# io.net
KiCad netlist of a schematic drawn in Altium Designer
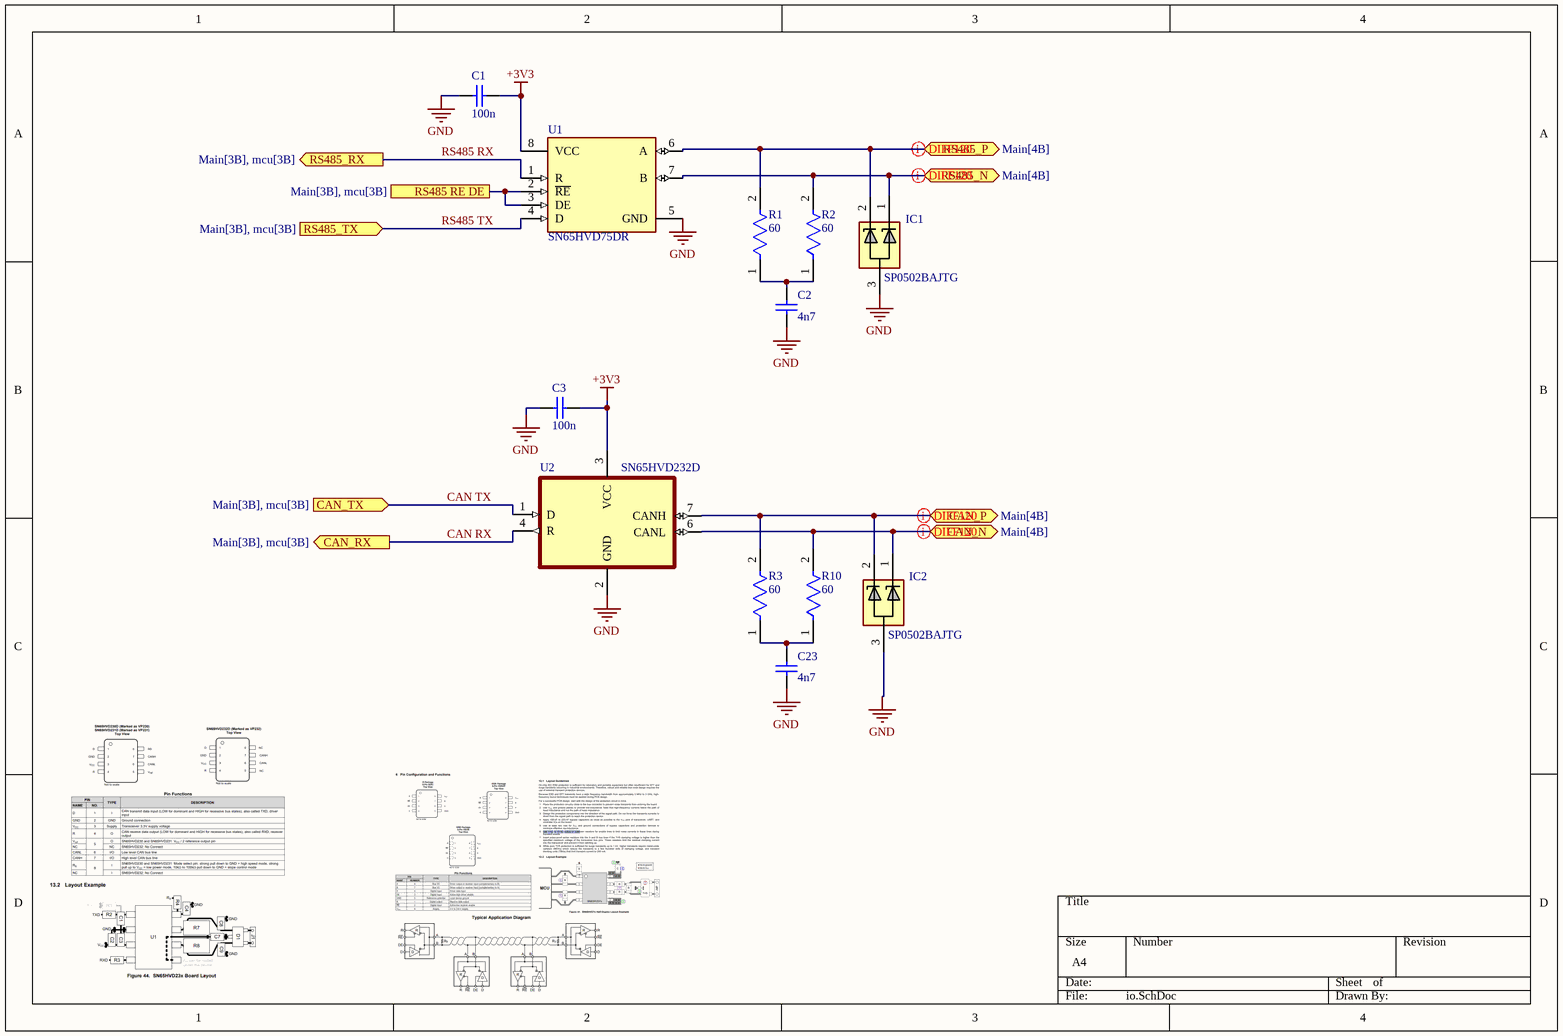
[diagram p0: io.SchDoc]

(export (version "E")
  (design (tool "Eeschema 10.0.6"))
  (components
    (comp (ref "C1")
      (value "100n")
      (footprint "CAPC1206(3216)170_M")
      (description "CAP 47nF 200V ±10% 1206 (3216 Metric) Thickness 1.7mm SMD")
      (fields (field (name "TOLERANCE") "Â±10%"))
      (libsource (lib "Altium Content Vault") (part "CAP"))
    )
    (comp (ref "C2")
      (value "4n7")
      (footprint "CAPC1206(3216)150_L")
      (description "CAP 1.8uF 10V ±5% 1206 (3216 Metric) Thickness 1.45mm SMD")
      (fields (field (name "TOLERANCE") "Â±5%"))
      (libsource (lib "Altium Content Vault") (part "CAP"))
    )
    (comp (ref "C3")
      (value "100n")
      (footprint "CAPC1206(3216)170_M")
      (description "CAP 47nF 200V ±10% 1206 (3216 Metric) Thickness 1.7mm SMD")
      (fields (field (name "TOLERANCE") "Â±10%"))
      (libsource (lib "Altium Content Vault") (part "CAP"))
    )
    (comp (ref "C23")
      (value "4n7")
      (footprint "CAPC1206(3216)150_L")
      (description "CAP 1.8uF 10V ±5% 1206 (3216 Metric) Thickness 1.45mm SMD")
      (fields (field (name "TOLERANCE") "Â±5%"))
      (libsource (lib "Altium Content Vault") (part "CAP"))
    )
    (comp (ref "IC1")
      (value "SP0502BAJTG")
      (footprint "SOT132P220X110-3N")
      (description "Integrated Circuit")
      (fields (field (name "MOUSER PART NUMBER") "576-SP0502BAJTG"))
      (libsource (lib "HydrogreenLibrary") (part "SP0502BAJTG"))
    )
    (comp (ref "IC2")
      (value "SP0502BAJTG")
      (footprint "SOT132P220X110-3N")
      (description "Integrated Circuit")
      (fields (field (name "MOUSER PART NUMBER") "576-SP0502BAJTG"))
      (libsource (lib "HydrogreenLibrary") (part "SP0502BAJTG"))
    )
    (comp (ref "R1")
      (value "60")
      (footprint "FP-RK73H2B-MFG")
      (description "40.2kΩ ±1% 0.25W Chip Resistor 1206 Thick Film AEC-Q200 Qualified")
      (fields (field (name "TOLERANCE") "1%"))
      (libsource (lib "Altium Content Vault") (part "1029c3af85768c4190bb7ad29bc67b5"))
    )
    (comp (ref "R2")
      (value "60")
      (footprint "FP-RK73H2B-MFG")
      (description "40.2kΩ ±1% 0.25W Chip Resistor 1206 Thick Film AEC-Q200 Qualified")
      (fields (field (name "TOLERANCE") "1%"))
      (libsource (lib "Altium Content Vault") (part "1029c3af85768c4190bb7ad29bc67b5"))
    )
    (comp (ref "R3")
      (value "60")
      (footprint "FP-RK73H2B-MFG")
      (description "40.2kΩ ±1% 0.25W Chip Resistor 1206 Thick Film AEC-Q200 Qualified")
      (fields (field (name "TOLERANCE") "1%"))
      (libsource (lib "Altium Content Vault") (part "1029c3af85768c4190bb7ad29bc67b5"))
    )
    (comp (ref "R10")
      (value "60")
      (footprint "FP-RK73H2B-MFG")
      (description "40.2kΩ ±1% 0.25W Chip Resistor 1206 Thick Film AEC-Q200 Qualified")
      (fields (field (name "TOLERANCE") "1%"))
      (libsource (lib "Altium Content Vault") (part "1029c3af85768c4190bb7ad29bc67b5"))
    )
    (comp (ref "U1")
      (value "SN65HVD75DR")
      (footprint "SN65HVD75DR")
      (description "Single Transmitter/Receiver RS-422/RS-485 8-Pin SOIC T/R")
      (fields (field (name "MANUFACTURER") "Texas Instruments"))
      (libsource (lib "HydrogreenLibrary") (part "SN65HVD75DR"))
    )
    (comp (ref "U2")
      (value "SN65HVD232D")
      (footprint "SN65HVD232D")
      (description "Texas Instruments - SN65HVD232DR - Can Transceiver, 1MBPS, 1/1, 3.3V, SOIC-8, Full Reel")
      (fields
        (field (name "MF") "Texas Instruments")
        (field (name "MANUFACTURER PART NUMBER") "SN65HVD232DR")
      )
      (libsource (lib "HydrogreenLibrary") (part "SN65HVD232D"))
    )
  )
  (nets
    (net (code "1") (name "+3V3") (class "Default")
      (node (ref "C1") (pin "1") (pinfunction "1_1") (pintype "passive"))
      (node (ref "C3") (pin "1") (pinfunction "1_1") (pintype "passive"))
      (node (ref "U1") (pin "8") (pinfunction "VCC_8") (pintype "power_in"))
      (node (ref "U2") (pin "3") (pinfunction "VCC_3") (pintype "power_in"))
    )
    (net (code "2") (name "/CAN RX") (class "Default")
      (node (ref "U2") (pin "4") (pinfunction "R_4") (pintype "output"))
    )
    (net (code "3") (name "/CAN TX") (class "Default")
      (node (ref "U2") (pin "1") (pinfunction "D_1") (pintype "input"))
    )
    (net (code "4") (name "/CAN_N") (class "Default")
      (node (ref "IC2") (pin "1") (pintype "passive"))
      (node (ref "R10") (pin "2") (pinfunction "2_2") (pintype "passive"))
      (node (ref "U2") (pin "6") (pinfunction "CANL_6") (pintype "bidirectional"))
    )
    (net (code "5") (name "/CAN_P") (class "Default")
      (node (ref "IC2") (pin "2") (pintype "passive"))
      (node (ref "R3") (pin "2") (pinfunction "2_2") (pintype "passive"))
      (node (ref "U2") (pin "7") (pinfunction "CANH_7") (pintype "bidirectional"))
    )
    (net (code "6") (name "/RS485 RE DE") (class "Default")
      (node (ref "U1") (pin "2") (pinfunction "~{RE}_2") (pintype "input"))
      (node (ref "U1") (pin "3") (pinfunction "DE_3") (pintype "input"))
    )
    (net (code "7") (name "/RS485 RX") (class "Default")
      (node (ref "U1") (pin "1") (pinfunction "R_1") (pintype "input"))
    )
    (net (code "8") (name "/RS485 TX") (class "Default")
      (node (ref "U1") (pin "4") (pinfunction "D_4") (pintype "input"))
    )
    (net (code "9") (name "/RS485_N") (class "Default")
      (node (ref "IC1") (pin "1") (pintype "passive"))
      (node (ref "R2") (pin "2") (pinfunction "2_2") (pintype "passive"))
      (node (ref "U1") (pin "7") (pinfunction "B_7") (pintype "bidirectional"))
    )
    (net (code "10") (name "/RS485_P") (class "Default")
      (node (ref "IC1") (pin "2") (pintype "passive"))
      (node (ref "R1") (pin "2") (pinfunction "2_2") (pintype "passive"))
      (node (ref "U1") (pin "6") (pinfunction "A_6") (pintype "bidirectional"))
    )
    (net (code "11") (name "GND") (class "Default")
      (node (ref "C1") (pin "2") (pinfunction "2_2") (pintype "passive"))
      (node (ref "C2") (pin "2") (pinfunction "2_2") (pintype "passive"))
      (node (ref "C23") (pin "2") (pinfunction "2_2") (pintype "passive"))
      (node (ref "C3") (pin "2") (pinfunction "2_2") (pintype "passive"))
      (node (ref "IC1") (pin "3") (pintype "passive"))
      (node (ref "IC2") (pin "3") (pintype "passive"))
      (node (ref "U1") (pin "5") (pinfunction "GND_5") (pintype "power_in"))
      (node (ref "U2") (pin "2") (pinfunction "GND_2") (pintype "power_in"))
    )
    (net (code "12") (name "Net-(C2-Pad1)") (class "Default")
      (node (ref "C2") (pin "1") (pinfunction "1_1") (pintype "passive"))
      (node (ref "R1") (pin "1") (pinfunction "1_1") (pintype "passive"))
      (node (ref "R2") (pin "1") (pinfunction "1_1") (pintype "passive"))
    )
    (net (code "13") (name "Net-(C23-Pad1)") (class "Default")
      (node (ref "C23") (pin "1") (pinfunction "1_1") (pintype "passive"))
      (node (ref "R10") (pin "1") (pinfunction "1_1") (pintype "passive"))
      (node (ref "R3") (pin "1") (pinfunction "1_1") (pintype "passive"))
    )
  )
)
